# Controlador-ArduUri.net
KiCad netlist of a schematic drawn in EAGLE
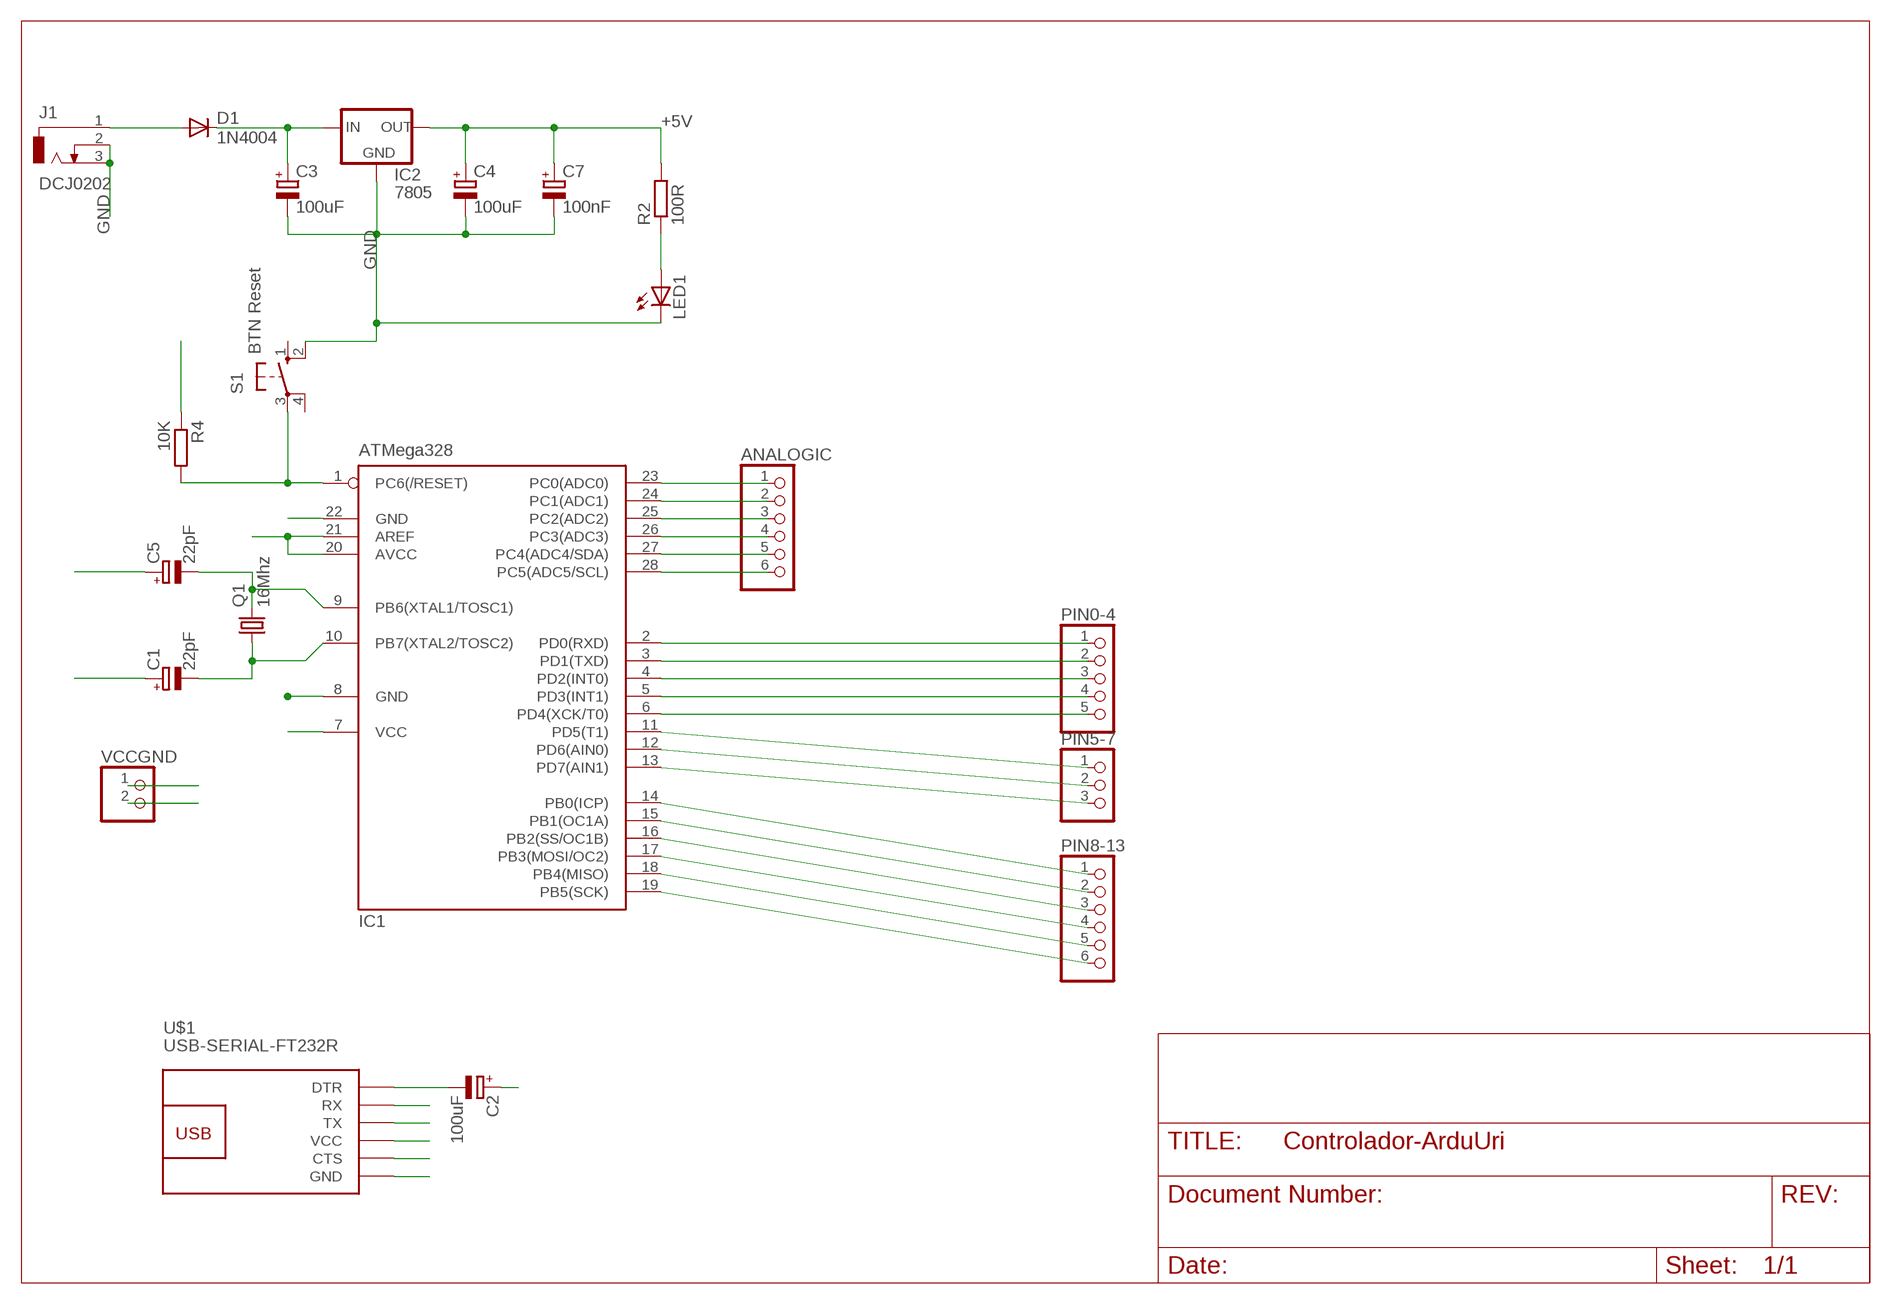
[diagram p0: schematic, sheet 1]

(export (version "E")
  (design (tool "Eeschema 10.0.6"))
  (components
    (comp (ref "ANALOGIC")
      (value "PINHD-1X6")
      (footprint "eagle-import:1X06")
      (libsource (lib "eagle-import") (part "PINHD-1X6"))
    )
    (comp (ref "C1")
      (value "22pF")
      (footprint "eagle-import:E2,5-5")
      (libsource (lib "eagle-import") (part "CPOL-EUE2.5-5"))
    )
    (comp (ref "C2")
      (value "100uF")
      (footprint "eagle-import:TAP5-50")
      (libsource (lib "eagle-import") (part "CPOL-EUTAP5-50"))
    )
    (comp (ref "C3")
      (value "100uF")
      (footprint "eagle-import:TAP5-50")
      (libsource (lib "eagle-import") (part "CPOL-EUTAP5-50"))
    )
    (comp (ref "C4")
      (value "100uF")
      (footprint "eagle-import:TAP5-50")
      (libsource (lib "eagle-import") (part "CPOL-EUTAP5-50"))
    )
    (comp (ref "C5")
      (value "22pF")
      (footprint "eagle-import:E2,5-5")
      (libsource (lib "eagle-import") (part "CPOL-EUE2.5-5"))
    )
    (comp (ref "C7")
      (value "100nF")
      (footprint "eagle-import:E2,5-5")
      (libsource (lib "eagle-import") (part "CPOL-EUE2.5-5"))
    )
    (comp (ref "D1")
      (value "1N4004")
      (footprint "eagle-import:DO41-10")
      (libsource (lib "eagle-import") (part "1N4004"))
    )
    (comp (ref "IC1")
      (value "ATMega328")
      (footprint "eagle-import:DIL28-3")
      (libsource (lib "eagle-import") (part "MEGA8-P"))
    )
    (comp (ref "IC2")
      (value "7805")
      (footprint "eagle-import:78XXL")
      (libsource (lib "eagle-import") (part "78XXL"))
    )
    (comp (ref "J1")
      (value "DCJ0202")
      (footprint "eagle-import:DCJ0202")
      (libsource (lib "eagle-import") (part "DCJ0202"))
    )
    (comp (ref "LED1")
      (value "LED5MM")
      (footprint "eagle-import:LED5MM")
      (libsource (lib "eagle-import") (part "LED5MM"))
    )
    (comp (ref "PIN0-4")
      (value "PINHD-1X5")
      (footprint "eagle-import:1X05")
      (libsource (lib "eagle-import") (part "PINHD-1X5"))
    )
    (comp (ref "PIN5-7")
      (value "PINHD-1X3")
      (footprint "eagle-import:1X03")
      (libsource (lib "eagle-import") (part "PINHD-1X3"))
    )
    (comp (ref "PIN8-13")
      (value "PINHD-1X6")
      (footprint "eagle-import:1X06")
      (libsource (lib "eagle-import") (part "PINHD-1X6"))
    )
    (comp (ref "Q1")
      (value "16Mhz")
      (footprint "eagle-import:HC49_S")
      (libsource (lib "eagle-import") (part "CRYSTALHC49S"))
    )
    (comp (ref "R2")
      (value "100R")
      (footprint "eagle-import:0204_7")
      (libsource (lib "eagle-import") (part "R-EU_0204/7"))
    )
    (comp (ref "R4")
      (value "10K")
      (footprint "eagle-import:0204_7")
      (libsource (lib "eagle-import") (part "R-EU_0204/7"))
    )
    (comp (ref "S1")
      (value "BTN Reset")
      (footprint "eagle-import:B3F-10XX")
      (fields (field (name "MPN") "B3F-1000"))
      (libsource (lib "eagle-import") (part "10-XX"))
    )
    (comp (ref "U$1")
      (value "USB-SERIAL-FT232R")
      (footprint "eagle-import:USB-SERIAL-FT232R")
      (libsource (lib "eagle-import") (part "USB-SERIAL-FT232R"))
    )
    (comp (ref "VCCGND")
      (value "PINHD-1X2")
      (footprint "eagle-import:1X02")
      (libsource (lib "eagle-import") (part "PINHD-1X2"))
    )
  )
  (nets
    (net (code "1") (name "/+5V") (class "Default")
      (node (ref "C4") (pin "+") (pinfunction "+_+") (pintype "passive"))
      (node (ref "C7") (pin "+") (pinfunction "+_+") (pintype "passive"))
      (node (ref "IC1") (pin "20") (pinfunction "AVCC_20") (pintype "power_in"))
      (node (ref "IC1") (pin "21") (pinfunction "AREF_21") (pintype "passive"))
      (node (ref "IC1") (pin "7") (pinfunction "VCC_7") (pintype "power_in"))
      (node (ref "IC2") (pin "OUT") (pinfunction "OUT_OUT") (pintype "passive"))
      (node (ref "R2") (pin "2") (pinfunction "2_2") (pintype "passive"))
      (node (ref "R4") (pin "1") (pinfunction "1_1") (pintype "passive"))
      (node (ref "U$1") (pin "4") (pinfunction "VCC_4") (pintype "power_in"))
      (node (ref "VCCGND") (pin "1") (pinfunction "1_1") (pintype "passive"))
    )
    (net (code "2") (name "/GND") (class "Default")
      (node (ref "C1") (pin "+") (pinfunction "+_+") (pintype "passive"))
      (node (ref "C3") (pin "-") (pinfunction "-_-") (pintype "passive"))
      (node (ref "C4") (pin "-") (pinfunction "-_-") (pintype "passive"))
      (node (ref "C5") (pin "+") (pinfunction "+_+") (pintype "passive"))
      (node (ref "C7") (pin "-") (pinfunction "-_-") (pintype "passive"))
      (node (ref "IC1") (pin "22") (pinfunction "GND_22") (pintype "power_in"))
      (node (ref "IC1") (pin "8") (pinfunction "GND_8") (pintype "power_in"))
      (node (ref "IC2") (pin "GND") (pinfunction "GND_GND") (pintype "input"))
      (node (ref "J1") (pin "2") (pinfunction "2_2") (pintype "passive"))
      (node (ref "J1") (pin "3") (pinfunction "3_3") (pintype "passive"))
      (node (ref "LED1") (pin "K") (pinfunction "C_K") (pintype "passive"))
      (node (ref "S1") (pin "2") (pinfunction "S1_2") (pintype "passive"))
      (node (ref "U$1") (pin "6") (pinfunction "GND_6") (pintype "bidirectional"))
      (node (ref "VCCGND") (pin "2") (pinfunction "2_2") (pintype "passive"))
    )
    (net (code "3") (name "/RESET") (class "Default")
      (node (ref "C2") (pin "+") (pinfunction "+_+") (pintype "passive"))
      (node (ref "IC1") (pin "1") (pinfunction "PC6(/RESET)_1") (pintype "bidirectional"))
      (node (ref "R4") (pin "2") (pinfunction "2_2") (pintype "passive"))
      (node (ref "S1") (pin "3") (pinfunction "P_3") (pintype "passive"))
    )
    (net (code "4") (name "/RX") (class "Default")
      (node (ref "IC1") (pin "2") (pinfunction "PD0(RXD)_2") (pintype "bidirectional"))
      (node (ref "PIN0-4") (pin "1") (pinfunction "1_1") (pintype "passive"))
      (node (ref "U$1") (pin "3") (pinfunction "TX_3") (pintype "bidirectional"))
    )
    (net (code "5") (name "/TX") (class "Default")
      (node (ref "IC1") (pin "3") (pinfunction "PD1(TXD)_3") (pintype "bidirectional"))
      (node (ref "PIN0-4") (pin "2") (pinfunction "2_2") (pintype "passive"))
      (node (ref "U$1") (pin "2") (pinfunction "RX_2") (pintype "bidirectional"))
    )
    (net (code "6") (name "Net-(C3-Pad+)") (class "Default")
      (node (ref "C3") (pin "+") (pinfunction "+_+") (pintype "passive"))
      (node (ref "D1") (pin "C") (pinfunction "C_C") (pintype "passive"))
      (node (ref "IC2") (pin "IN") (pinfunction "IN_IN") (pintype "input"))
    )
    (net (code "7") (name "Net-(D1-PadA)") (class "Default")
      (node (ref "D1") (pin "A") (pinfunction "A_A") (pintype "passive"))
      (node (ref "J1") (pin "1") (pinfunction "1_1") (pintype "passive"))
    )
    (net (code "8") (name "Net-(IC1-PB0(ICP))") (class "Default")
      (node (ref "IC1") (pin "14") (pinfunction "PB0(ICP)_14") (pintype "bidirectional"))
      (node (ref "PIN8-13") (pin "1") (pinfunction "1_1") (pintype "passive"))
    )
    (net (code "9") (name "Net-(IC1-PB1(OC1A))") (class "Default")
      (node (ref "IC1") (pin "15") (pinfunction "PB1(OC1A)_15") (pintype "bidirectional"))
      (node (ref "PIN8-13") (pin "2") (pinfunction "2_2") (pintype "passive"))
    )
    (net (code "10") (name "Net-(IC1-PB2(SS{slash}OC1B))") (class "Default")
      (node (ref "IC1") (pin "16") (pinfunction "PB2(SS/OC1B)_16") (pintype "bidirectional"))
      (node (ref "PIN8-13") (pin "3") (pinfunction "3_3") (pintype "passive"))
    )
    (net (code "11") (name "Net-(IC1-PB3(MOSI{slash}OC2))") (class "Default")
      (node (ref "IC1") (pin "17") (pinfunction "PB3(MOSI/OC2)_17") (pintype "bidirectional"))
      (node (ref "PIN8-13") (pin "4") (pinfunction "4_4") (pintype "passive"))
    )
    (net (code "12") (name "Net-(IC1-PB4(MISO))") (class "Default")
      (node (ref "IC1") (pin "18") (pinfunction "PB4(MISO)_18") (pintype "bidirectional"))
      (node (ref "PIN8-13") (pin "5") (pinfunction "5_5") (pintype "passive"))
    )
    (net (code "13") (name "Net-(IC1-PB5(SCK))") (class "Default")
      (node (ref "IC1") (pin "19") (pinfunction "PB5(SCK)_19") (pintype "bidirectional"))
      (node (ref "PIN8-13") (pin "6") (pinfunction "6_6") (pintype "passive"))
    )
    (net (code "14") (name "Net-(IC1-PB6(XTAL1{slash}TOSC1))") (class "Default")
      (node (ref "C5") (pin "-") (pinfunction "-_-") (pintype "passive"))
      (node (ref "IC1") (pin "9") (pinfunction "PB6(XTAL1/TOSC1)_9") (pintype "bidirectional"))
      (node (ref "Q1") (pin "2") (pinfunction "2_2") (pintype "passive"))
    )
    (net (code "15") (name "Net-(IC1-PB7(XTAL2{slash}TOSC2))") (class "Default")
      (node (ref "C1") (pin "-") (pinfunction "-_-") (pintype "passive"))
      (node (ref "IC1") (pin "10") (pinfunction "PB7(XTAL2/TOSC2)_10") (pintype "bidirectional"))
      (node (ref "Q1") (pin "1") (pinfunction "1_1") (pintype "passive"))
    )
    (net (code "16") (name "Net-(IC1-PC0(ADC0))") (class "Default")
      (node (ref "ANALOGIC") (pin "1") (pinfunction "1_1") (pintype "passive"))
      (node (ref "IC1") (pin "23") (pinfunction "PC0(ADC0)_23") (pintype "bidirectional"))
    )
    (net (code "17") (name "Net-(IC1-PC1(ADC1))") (class "Default")
      (node (ref "ANALOGIC") (pin "2") (pinfunction "2_2") (pintype "passive"))
      (node (ref "IC1") (pin "24") (pinfunction "PC1(ADC1)_24") (pintype "bidirectional"))
    )
    (net (code "18") (name "Net-(IC1-PC2(ADC2))") (class "Default")
      (node (ref "ANALOGIC") (pin "3") (pinfunction "3_3") (pintype "passive"))
      (node (ref "IC1") (pin "25") (pinfunction "PC2(ADC2)_25") (pintype "bidirectional"))
    )
    (net (code "19") (name "Net-(IC1-PC3(ADC3))") (class "Default")
      (node (ref "ANALOGIC") (pin "4") (pinfunction "4_4") (pintype "passive"))
      (node (ref "IC1") (pin "26") (pinfunction "PC3(ADC3)_26") (pintype "bidirectional"))
    )
    (net (code "20") (name "Net-(IC1-PC4(ADC4{slash}SDA))") (class "Default")
      (node (ref "ANALOGIC") (pin "5") (pinfunction "5_5") (pintype "passive"))
      (node (ref "IC1") (pin "27") (pinfunction "PC4(ADC4/SDA)_27") (pintype "bidirectional"))
    )
    (net (code "21") (name "Net-(IC1-PC5(ADC5{slash}SCL))") (class "Default")
      (node (ref "ANALOGIC") (pin "6") (pinfunction "6_6") (pintype "passive"))
      (node (ref "IC1") (pin "28") (pinfunction "PC5(ADC5/SCL)_28") (pintype "bidirectional"))
    )
    (net (code "22") (name "Net-(IC1-PD2(INT0))") (class "Default")
      (node (ref "IC1") (pin "4") (pinfunction "PD2(INT0)_4") (pintype "bidirectional"))
      (node (ref "PIN0-4") (pin "3") (pinfunction "3_3") (pintype "passive"))
    )
    (net (code "23") (name "Net-(IC1-PD3(INT1))") (class "Default")
      (node (ref "IC1") (pin "5") (pinfunction "PD3(INT1)_5") (pintype "bidirectional"))
      (node (ref "PIN0-4") (pin "4") (pinfunction "4_4") (pintype "passive"))
    )
    (net (code "24") (name "Net-(IC1-PD4(XCK{slash}T0))") (class "Default")
      (node (ref "IC1") (pin "6") (pinfunction "PD4(XCK/T0)_6") (pintype "bidirectional"))
      (node (ref "PIN0-4") (pin "5") (pinfunction "5_5") (pintype "passive"))
    )
    (net (code "25") (name "Net-(IC1-PD5(T1))") (class "Default")
      (node (ref "IC1") (pin "11") (pinfunction "PD5(T1)_11") (pintype "bidirectional"))
      (node (ref "PIN5-7") (pin "1") (pinfunction "1_1") (pintype "passive"))
    )
    (net (code "26") (name "Net-(IC1-PD6(AIN0))") (class "Default")
      (node (ref "IC1") (pin "12") (pinfunction "PD6(AIN0)_12") (pintype "bidirectional"))
      (node (ref "PIN5-7") (pin "2") (pinfunction "2_2") (pintype "passive"))
    )
    (net (code "27") (name "Net-(IC1-PD7(AIN1))") (class "Default")
      (node (ref "IC1") (pin "13") (pinfunction "PD7(AIN1)_13") (pintype "bidirectional"))
      (node (ref "PIN5-7") (pin "3") (pinfunction "3_3") (pintype "passive"))
    )
    (net (code "28") (name "Net-(LED1-PadA)") (class "Default")
      (node (ref "LED1") (pin "A") (pinfunction "A_A") (pintype "passive"))
      (node (ref "R2") (pin "1") (pinfunction "1_1") (pintype "passive"))
    )
    (net (code "29") (name "Net-(U$1-DTR)") (class "Default")
      (node (ref "C2") (pin "-") (pinfunction "-_-") (pintype "passive"))
      (node (ref "U$1") (pin "1") (pinfunction "DTR_1") (pintype "bidirectional"))
    )
    (net (code "30") (name "unconnected-(S1-P1-Pad4)") (class "Default")
      (node (ref "S1") (pin "4") (pinfunction "P1_4") (pintype "passive"))
    )
    (net (code "31") (name "unconnected-(S1-S-Pad1)") (class "Default")
      (node (ref "S1") (pin "1") (pinfunction "S_1") (pintype "passive"))
    )
    (net (code "32") (name "unconnected-(U$1-CTS-Pad5)") (class "Default")
      (node (ref "U$1") (pin "5") (pinfunction "CTS_5") (pintype "bidirectional"))
    )
  )
)
